# Gagabiro_POC_amp_main.net
KiCad netlist of a schematic drawn in Altium Designer
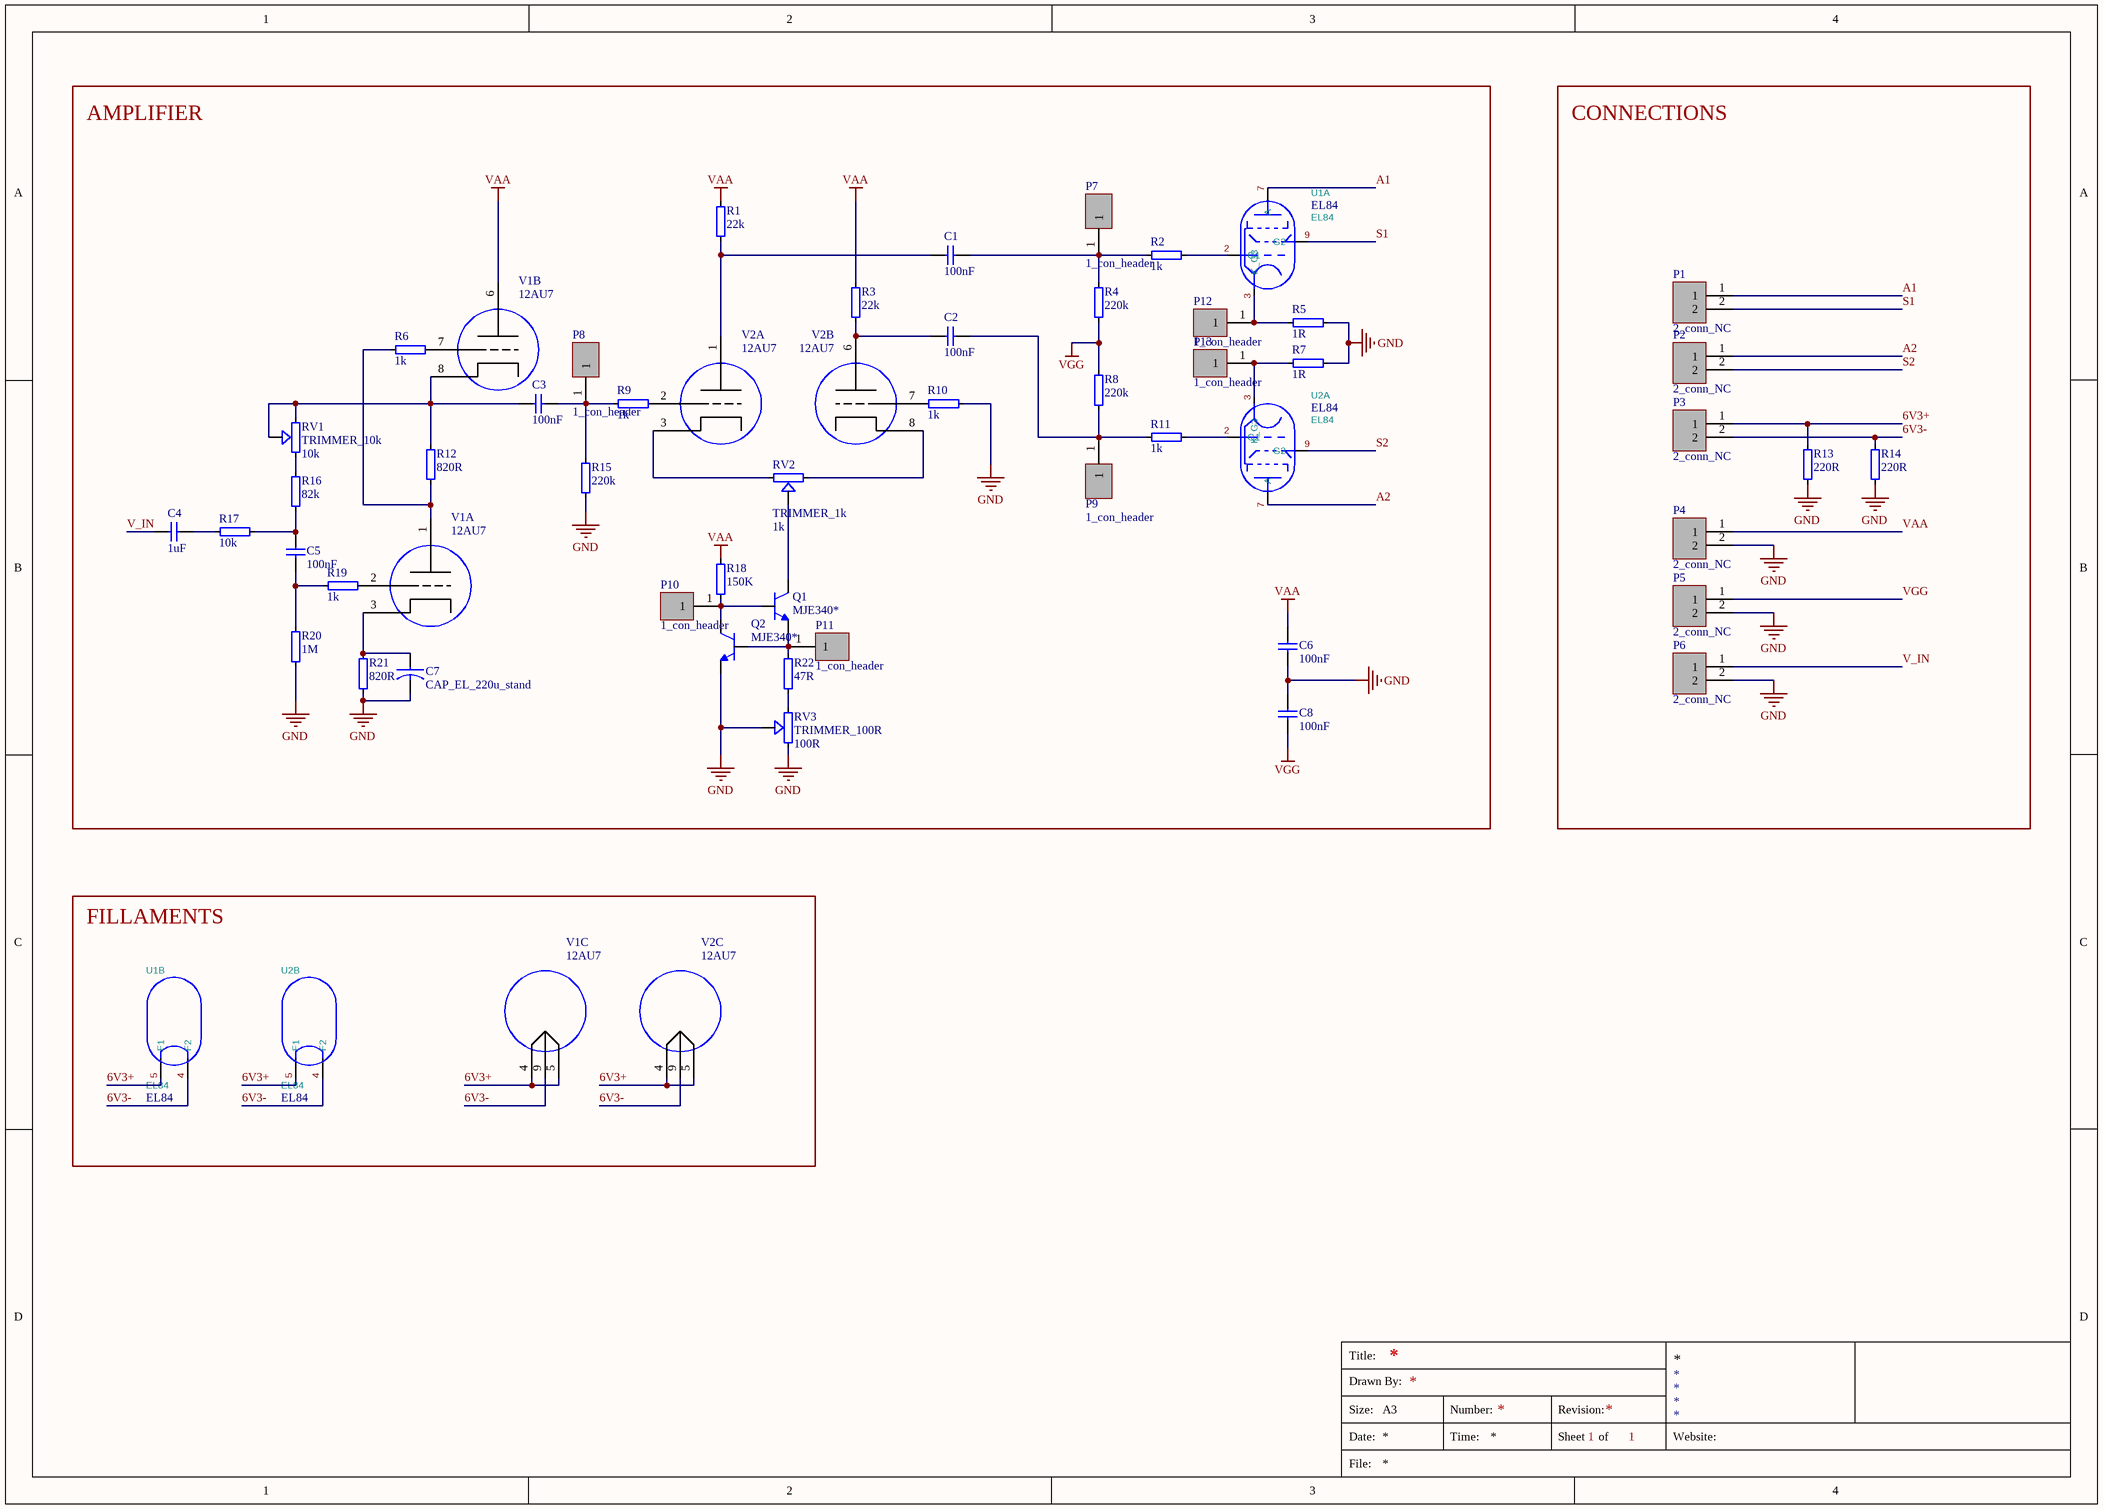
[diagram p0: Gagabiro_POC_amp_main.SchDoc]

(export (version "E")
  (design (tool "Eeschema 10.0.6"))
  (components
    (comp (ref "C1")
      (value "100nF")
      (footprint "CAP_panassonic_100n_450V")
      (description "Capacitor, Silver Mica")
      (fields (field (name "PART NUMBER") "CMICA_47PF"))
      (libsource (lib "Persephone_Integrated_Library") (part "CAP_POLY_100n"))
    )
    (comp (ref "C2")
      (value "100nF")
      (footprint "CAP_panassonic_100n_450V")
      (description "Capacitor, Silver Mica")
      (fields (field (name "PART NUMBER") "CMICA_47PF"))
      (libsource (lib "Persephone_Integrated_Library") (part "CAP_POLY_100n"))
    )
    (comp (ref "C3")
      (value "100nF")
      (footprint "CAP_panassonic_100n_450V")
      (description "Capacitor, Silver Mica")
      (fields (field (name "PART NUMBER") "CMICA_47PF"))
      (libsource (lib "Persephone_Integrated_Library") (part "CAP_POLY_100n"))
    )
    (comp (ref "C4")
      (value "1uF")
      (footprint "CAP_panassonic_1u_450V")
      (description "Capacitor, Silver Mica")
      (fields (field (name "PART NUMBER") "CMICA_47PF"))
      (libsource (lib "Persephone_Integrated_Library") (part "CAP_POLY_1u"))
    )
    (comp (ref "C5")
      (value "100nF")
      (footprint "CAP_panassonic_100n_450V")
      (description "Capacitor, Silver Mica")
      (fields (field (name "PART NUMBER") "CMICA_47PF"))
      (libsource (lib "Persephone_Integrated_Library") (part "CAP_POLY_100n"))
    )
    (comp (ref "C6")
      (value "100nF")
      (footprint "CAP_panassonic_100n_450V")
      (description "Capacitor, Silver Mica")
      (fields (field (name "PART NUMBER") "CMICA_47PF"))
      (libsource (lib "Persephone_Integrated_Library") (part "CAP_POLY_100n"))
    )
    (comp (ref "C7")
      (value "CAP_EL_220u_stand")
      (footprint "CAPPRD500W50D630H1120_stand")
      (description "220F 16V Aluminum Electrolytic Capacitors Radial, Can 1000 Hrs @ 105C")
      (fields (field (name "MP") "EEU-HD1C221B") (field (name "MF") "Panasonic"))
      (libsource (lib "Persephone_Integrated_Library") (part "CAP_EL_220u_stand"))
    )
    (comp (ref "C8")
      (value "100nF")
      (footprint "CAP_panassonic_100n_450V")
      (description "Capacitor, Silver Mica")
      (fields (field (name "PART NUMBER") "CMICA_47PF"))
      (libsource (lib "Persephone_Integrated_Library") (part "CAP_POLY_100n"))
    )
    (comp (ref "P1")
      (value "2_conn_NC")
      (footprint "2_conn_NC")
      (description "Connector Header Surface Mount, Right Angle 2 position 0.079 (2.00mm)")
      (fields (field (name "MP") "S2B-PH-SM4-TB") (field (name "MF") "JST Sales"))
      (libsource (lib "Gagabiro_Integrated_Library") (part "2_conn_NC"))
    )
    (comp (ref "P2")
      (value "2_conn_NC")
      (footprint "2_conn_NC")
      (description "Connector Header Surface Mount, Right Angle 2 position 0.079 (2.00mm)")
      (fields (field (name "MP") "S2B-PH-SM4-TB") (field (name "MF") "JST Sales"))
      (libsource (lib "Gagabiro_Integrated_Library") (part "2_conn_NC"))
    )
    (comp (ref "P3")
      (value "2_conn_NC")
      (footprint "2_conn_NC")
      (description "Connector Header Surface Mount, Right Angle 2 position 0.079 (2.00mm)")
      (fields (field (name "MP") "S2B-PH-SM4-TB") (field (name "MF") "JST Sales"))
      (libsource (lib "Gagabiro_Integrated_Library") (part "2_conn_NC"))
    )
    (comp (ref "P4")
      (value "2_conn_NC")
      (footprint "2_conn_NC")
      (description "Connector Header Surface Mount, Right Angle 2 position 0.079 (2.00mm)")
      (fields (field (name "MP") "S2B-PH-SM4-TB") (field (name "MF") "JST Sales"))
      (libsource (lib "Gagabiro_Integrated_Library") (part "2_conn_NC"))
    )
    (comp (ref "P5")
      (value "2_conn_NC")
      (footprint "2_conn_NC")
      (description "Connector Header Surface Mount, Right Angle 2 position 0.079 (2.00mm)")
      (fields (field (name "MP") "S2B-PH-SM4-TB") (field (name "MF") "JST Sales"))
      (libsource (lib "Gagabiro_Integrated_Library") (part "2_conn_NC"))
    )
    (comp (ref "P6")
      (value "2_conn_NC")
      (footprint "2_conn_NC")
      (description "Connector Header Surface Mount, Right Angle 2 position 0.079 (2.00mm)")
      (fields (field (name "MP") "S2B-PH-SM4-TB") (field (name "MF") "JST Sales"))
      (libsource (lib "Gagabiro_Integrated_Library") (part "2_conn_NC"))
    )
    (comp (ref "P7")
      (value "1_con_header")
      (footprint "SAMTEC_MTMM-101-X-X-S-X")
      (description "Connector Header Surface Mount, Right Angle 2 position 0.079 (2.00mm)")
      (fields (field (name "MP") "S2B-PH-SM4-TB") (field (name "MF") "JST Sales"))
      (libsource (lib "") (part "1_con_header_3"))
    )
    (comp (ref "P8")
      (value "1_con_header")
      (footprint "SAMTEC_MTMM-101-X-X-S-X")
      (description "Connector Header Surface Mount, Right Angle 2 position 0.079 (2.00mm)")
      (fields (field (name "MP") "S2B-PH-SM4-TB") (field (name "MF") "JST Sales"))
      (libsource (lib "") (part "1_con_header_3"))
    )
    (comp (ref "P9")
      (value "1_con_header")
      (footprint "SAMTEC_MTMM-101-X-X-S-X")
      (description "Connector Header Surface Mount, Right Angle 2 position 0.079 (2.00mm)")
      (fields (field (name "MP") "S2B-PH-SM4-TB") (field (name "MF") "JST Sales"))
      (libsource (lib "") (part "1_con_header_2"))
    )
    (comp (ref "P10")
      (value "1_con_header")
      (footprint "SAMTEC_MTMM-101-X-X-S-X")
      (description "Connector Header Surface Mount, Right Angle 2 position 0.079 (2.00mm)")
      (fields (field (name "MP") "S2B-PH-SM4-TB") (field (name "MF") "JST Sales"))
      (libsource (lib "Gagabiro") (part "1_con_header"))
    )
    (comp (ref "P11")
      (value "1_con_header")
      (footprint "SAMTEC_MTMM-101-X-X-S-X")
      (description "Connector Header Surface Mount, Right Angle 2 position 0.079 (2.00mm)")
      (fields (field (name "MP") "S2B-PH-SM4-TB") (field (name "MF") "JST Sales"))
      (libsource (lib "") (part "1_con_header_1"))
    )
    (comp (ref "P12")
      (value "1_con_header")
      (footprint "SAMTEC_MTMM-101-X-X-S-X")
      (description "Connector Header Surface Mount, Right Angle 2 position 0.079 (2.00mm)")
      (fields (field (name "MP") "S2B-PH-SM4-TB") (field (name "MF") "JST Sales"))
      (libsource (lib "Gagabiro") (part "1_con_header"))
    )
    (comp (ref "P13")
      (value "1_con_header")
      (footprint "SAMTEC_MTMM-101-X-X-S-X")
      (description "Connector Header Surface Mount, Right Angle 2 position 0.079 (2.00mm)")
      (fields (field (name "MP") "S2B-PH-SM4-TB") (field (name "MF") "JST Sales"))
      (libsource (lib "Gagabiro") (part "1_con_header"))
    )
    (comp (ref "Q1")
      (value "MJE340*")
      (footprint "TO126")
      (description "Bipolar (BJT) Transistor NPN 300 V 500 mA - 20.8 W Through Hole SOT-32-3")
      (fields (field (name "MF") "STMicroelectronics") (field (name "MP") "MJE340"))
      (libsource (lib "Persephone_Integrated_Library") (part "MJE340*"))
    )
    (comp (ref "Q2")
      (value "MJE340*")
      (footprint "TO126")
      (description "Bipolar (BJT) Transistor NPN 300 V 500 mA - 20.8 W Through Hole SOT-32-3")
      (fields (field (name "MF") "STMicroelectronics") (field (name "MP") "MJE340"))
      (libsource (lib "Persephone_Integrated_Library") (part "MJE340*"))
    )
    (comp (ref "R1")
      (value "22k")
      (footprint "RES_2W_vertical")
      (description "Resistor, 2W")
      (fields (field (name "PART NUMBER") "R2W") (field (name "AUTHOR") "colombari"))
      (libsource (lib "Gagabiro_Integrated_Library") (part "R_2W_vertical_22k"))
    )
    (comp (ref "R2")
      (value "1k")
      (footprint "RES_2W_vertical")
      (description "Resistor, 2W")
      (fields (field (name "PART NUMBER") "R2W") (field (name "AUTHOR") "colombari"))
      (libsource (lib "Gagabiro_Integrated_Library") (part "R_2W_vertical_1k"))
    )
    (comp (ref "R3")
      (value "22k")
      (footprint "RES_2W_vertical")
      (description "Resistor, 2W")
      (fields (field (name "PART NUMBER") "R2W") (field (name "AUTHOR") "colombari"))
      (libsource (lib "Gagabiro_Integrated_Library") (part "R_2W_vertical_22k"))
    )
    (comp (ref "R4")
      (value "220k")
      (footprint "RES_2W_vertical")
      (description "Resistor, 2W")
      (fields (field (name "PART NUMBER") "R2W") (field (name "AUTHOR") "colombari"))
      (libsource (lib "Gagabiro_Integrated_Library") (part "R_2W_vertical_220k"))
    )
    (comp (ref "R5")
      (value "1R")
      (footprint "RES_2W_vertical")
      (description "Resistor, 2W")
      (fields (field (name "PART NUMBER") "R2W") (field (name "AUTHOR") "colombari"))
      (libsource (lib "Gagabiro_Integrated_Library") (part "R_2W_vertical_1R"))
    )
    (comp (ref "R6")
      (value "1k")
      (footprint "RES_2W_vertical")
      (description "Resistor, 2W")
      (fields (field (name "PART NUMBER") "R2W") (field (name "AUTHOR") "colombari"))
      (libsource (lib "Gagabiro_Integrated_Library") (part "R_2W_vertical_1k"))
    )
    (comp (ref "R7")
      (value "1R")
      (footprint "RES_2W_vertical")
      (description "Resistor, 2W")
      (fields (field (name "PART NUMBER") "R2W") (field (name "AUTHOR") "colombari"))
      (libsource (lib "Gagabiro_Integrated_Library") (part "R_2W_vertical_1R"))
    )
    (comp (ref "R8")
      (value "220k")
      (footprint "RES_2W_vertical")
      (description "Resistor, 2W")
      (fields (field (name "PART NUMBER") "R2W") (field (name "AUTHOR") "colombari"))
      (libsource (lib "Gagabiro_Integrated_Library") (part "R_2W_vertical_220k"))
    )
    (comp (ref "R9")
      (value "1k")
      (footprint "RES_2W_vertical")
      (description "Resistor, 2W")
      (fields (field (name "PART NUMBER") "R2W") (field (name "AUTHOR") "colombari"))
      (libsource (lib "Gagabiro_Integrated_Library") (part "R_2W_vertical_1k"))
    )
    (comp (ref "R10")
      (value "1k")
      (footprint "RES_2W_vertical")
      (description "Resistor, 2W")
      (fields (field (name "PART NUMBER") "R2W") (field (name "AUTHOR") "colombari"))
      (libsource (lib "Gagabiro_Integrated_Library") (part "R_2W_vertical_1k"))
    )
    (comp (ref "R11")
      (value "1k")
      (footprint "RES_2W_vertical")
      (description "Resistor, 2W")
      (fields (field (name "PART NUMBER") "R2W") (field (name "AUTHOR") "colombari"))
      (libsource (lib "Gagabiro_Integrated_Library") (part "R_2W_vertical_1k"))
    )
    (comp (ref "R12")
      (value "820R")
      (footprint "RES_2W_vertical")
      (description "Resistor, 2W")
      (fields (field (name "PART NUMBER") "R2W") (field (name "AUTHOR") "colombari"))
      (libsource (lib "Gagabiro_Integrated_Library") (part "R_2W_vertical_820R"))
    )
    (comp (ref "R13")
      (value "220R")
      (footprint "RES_2W_vertical")
      (description "Resistor, 2W")
      (fields (field (name "PART NUMBER") "R2W") (field (name "AUTHOR") "colombari"))
      (libsource (lib "Persephone_Integrated_Library") (part "R_2W_vertical_220R"))
    )
    (comp (ref "R14")
      (value "220R")
      (footprint "RES_2W_vertical")
      (description "Resistor, 2W")
      (fields (field (name "PART NUMBER") "R2W") (field (name "AUTHOR") "colombari"))
      (libsource (lib "Persephone_Integrated_Library") (part "R_2W_vertical_220R"))
    )
    (comp (ref "R15")
      (value "220k")
      (footprint "RES_2W_vertical")
      (description "Resistor, 2W")
      (fields (field (name "PART NUMBER") "R2W") (field (name "AUTHOR") "colombari"))
      (libsource (lib "Gagabiro_Integrated_Library") (part "R_2W_vertical_220k"))
    )
    (comp (ref "R16")
      (value "82k")
      (footprint "RES_2W_vertical")
      (description "Resistor, 2W")
      (fields (field (name "PART NUMBER") "R2W") (field (name "AUTHOR") "colombari"))
      (libsource (lib "Gagabiro_Integrated_Library") (part "R_2W_vertical_82k"))
    )
    (comp (ref "R17")
      (value "10k")
      (footprint "RES_2W_vertical")
      (description "Resistor, 2W")
      (fields (field (name "PART NUMBER") "R2W") (field (name "AUTHOR") "colombari"))
      (libsource (lib "Gagabiro_Integrated_Library") (part "R_2W_vertical_10k"))
    )
    (comp (ref "R18")
      (value "150K")
      (footprint "RES_2W_vertical")
      (description "Resistor, 2W")
      (fields (field (name "PART NUMBER") "R2W") (field (name "AUTHOR") "colombari"))
      (libsource (lib "Gagabiro_Integrated_Library") (part "R_2W_vertical_150K"))
    )
    (comp (ref "R19")
      (value "1k")
      (footprint "RES_2W_vertical")
      (description "Resistor, 2W")
      (fields (field (name "PART NUMBER") "R2W") (field (name "AUTHOR") "colombari"))
      (libsource (lib "Gagabiro_Integrated_Library") (part "R_2W_vertical_1k"))
    )
    (comp (ref "R20")
      (value "1M")
      (footprint "RES_2W_vertical")
      (description "Resistor, 2W")
      (fields (field (name "PART NUMBER") "R2W") (field (name "AUTHOR") "colombari"))
      (libsource (lib "Gagabiro_Integrated_Library") (part "R_2W_vertical_1M"))
    )
    (comp (ref "R21")
      (value "820R")
      (footprint "RES_2W_vertical")
      (description "Resistor, 2W")
      (fields (field (name "PART NUMBER") "R2W") (field (name "AUTHOR") "colombari"))
      (libsource (lib "Gagabiro_Integrated_Library") (part "R_2W_vertical_820R"))
    )
    (comp (ref "R22")
      (value "47R")
      (footprint "RES_2W_vertical")
      (description "Resistor, 2W")
      (fields (field (name "PART NUMBER") "R2W") (field (name "AUTHOR") "colombari"))
      (libsource (lib "Gagabiro_Integrated_Library") (part "R_2W_vertical_47R"))
    )
    (comp (ref "RV1")
      (value "TRIMMER_10k")
      (footprint "TRIM_PV36W204C01B00 - duplicate")
      (description "TRIMMER")
      (fields
        (field (name "MF") "Bourns Electronics")
        (field (name "MP") "PV36W204C01B00.")
        (field (name "ALTIUM_VALUE") "10k")
      )
      (libsource (lib "Persephone_Integrated_Library") (part "TRIMMER_10k"))
    )
    (comp (ref "RV2")
      (value "TRIMMER_1k")
      (footprint "TRIM_PV36W204C01B00 - duplicate")
      (description "TRIMMER")
      (fields
        (field (name "MF") "Bourns Electronics")
        (field (name "MP") "PV36W204C01B00.")
        (field (name "ALTIUM_VALUE") "1k")
      )
      (libsource (lib "Persephone_Integrated_Library") (part "TRIMMER_1k"))
    )
    (comp (ref "RV3")
      (value "TRIMMER_100R")
      (footprint "TRIM_PV36W204C01B00 - duplicate")
      (description "TRIMMER")
      (fields
        (field (name "MF") "Bourns Electronics")
        (field (name "MP") "PV36W204C01B00.")
        (field (name "ALTIUM_VALUE") "100R")
      )
      (libsource (lib "Persephone") (part "TRIMMER_100R"))
    )
    (comp (ref "U1")
      (value "EL84")
      (footprint "EL84")
      (fields (field (name "ALTIUM_VALUE") "EL84"))
      (libsource (lib "Gagabiro_Integrated_Library") (part "EL84"))
    )
    (comp (ref "U2")
      (value "EL84")
      (footprint "EL84")
      (fields (field (name "ALTIUM_VALUE") "EL84"))
      (libsource (lib "Gagabiro_Integrated_Library") (part "EL84"))
    )
    (comp (ref "V1")
      (value "12AU7")
      (footprint "12A_7")
      (description "TUNGSOL 12AU7 NEW PRD PREAMP TB")
      (fields (field (name "MF") "RCA") (field (name "MP") "12AX7"))
      (libsource (lib "") (part "12AU7_1"))
    )
    (comp (ref "V2")
      (value "12AU7")
      (footprint "12A_7")
      (description "TUNGSOL 12AU7 NEW PRD PREAMP TB")
      (fields (field (name "MF") "RCA") (field (name "MP") "12AX7"))
      (libsource (lib "Gagabiro_Integrated_Library") (part "12AU7"))
    )
  )
  (nets
    (net (code "1") (name "/6V3+") (class "Default")
      (node (ref "P3") (pin "1") (pinfunction "1_1") (pintype "passive"))
      (node (ref "R13") (pin "2") (pinfunction "2_2") (pintype "passive"))
      (node (ref "U1") (pin "5") (pinfunction "F1_5") (pintype "passive"))
      (node (ref "U2") (pin "5") (pinfunction "F1_5") (pintype "passive"))
      (node (ref "V1") (pin "4") (pinfunction "4_4") (pintype "passive"))
      (node (ref "V1") (pin "5") (pinfunction "5_5") (pintype "passive"))
      (node (ref "V2") (pin "4") (pinfunction "4_4") (pintype "passive"))
      (node (ref "V2") (pin "5") (pinfunction "5_5") (pintype "passive"))
    )
    (net (code "2") (name "/6V3-") (class "Default")
      (node (ref "P3") (pin "2") (pinfunction "2_2") (pintype "passive"))
      (node (ref "R14") (pin "2") (pinfunction "2_2") (pintype "passive"))
      (node (ref "U1") (pin "4") (pinfunction "F2_4") (pintype "passive"))
      (node (ref "U2") (pin "4") (pinfunction "F2_4") (pintype "passive"))
      (node (ref "V1") (pin "9") (pinfunction "9_9") (pintype "passive"))
      (node (ref "V2") (pin "9") (pinfunction "9_9") (pintype "passive"))
    )
    (net (code "3") (name "/A1") (class "Default")
      (node (ref "P1") (pin "1") (pinfunction "1_1") (pintype "passive"))
      (node (ref "U1") (pin "7") (pinfunction "A_7") (pintype "passive"))
    )
    (net (code "4") (name "/A2") (class "Default")
      (node (ref "P2") (pin "1") (pinfunction "1_1") (pintype "passive"))
      (node (ref "U2") (pin "7") (pinfunction "A_7") (pintype "passive"))
    )
    (net (code "5") (name "/S1") (class "Default")
      (node (ref "P1") (pin "2") (pinfunction "2_2") (pintype "passive"))
      (node (ref "U1") (pin "9") (pinfunction "G2_9") (pintype "passive"))
    )
    (net (code "6") (name "/S2") (class "Default")
      (node (ref "P2") (pin "2") (pinfunction "2_2") (pintype "passive"))
      (node (ref "U2") (pin "9") (pinfunction "G2_9") (pintype "passive"))
    )
    (net (code "7") (name "/V_IN") (class "Default")
      (node (ref "C4") (pin "1") (pinfunction "1_1") (pintype "passive"))
      (node (ref "P6") (pin "1") (pinfunction "1_1") (pintype "passive"))
    )
    (net (code "8") (name "GND") (class "Default")
      (node (ref "C6") (pin "1") (pinfunction "1_1") (pintype "passive"))
      (node (ref "C7") (pin "N") (pinfunction "N_N") (pintype "passive"))
      (node (ref "C8") (pin "1") (pinfunction "1_1") (pintype "passive"))
      (node (ref "P4") (pin "2") (pinfunction "2_2") (pintype "passive"))
      (node (ref "P5") (pin "2") (pinfunction "2_2") (pintype "passive"))
      (node (ref "P6") (pin "2") (pinfunction "2_2") (pintype "passive"))
      (node (ref "Q2") (pin "1") (pinfunction "E_1") (pintype "passive"))
      (node (ref "R10") (pin "2") (pinfunction "2_2") (pintype "passive"))
      (node (ref "R13") (pin "1") (pinfunction "1_1") (pintype "passive"))
      (node (ref "R14") (pin "1") (pinfunction "1_1") (pintype "passive"))
      (node (ref "R15") (pin "1") (pinfunction "1_1") (pintype "passive"))
      (node (ref "R20") (pin "1") (pinfunction "1_1") (pintype "passive"))
      (node (ref "R21") (pin "1") (pinfunction "1_1") (pintype "passive"))
      (node (ref "R5") (pin "2") (pinfunction "2_2") (pintype "passive"))
      (node (ref "R7") (pin "2") (pinfunction "2_2") (pintype "passive"))
      (node (ref "RV3") (pin "1") (pinfunction "1_1") (pintype "passive"))
      (node (ref "RV3") (pin "2") (pinfunction "2_2") (pintype "passive"))
    )
    (net (code "9") (name "Net-(C1-Pad1)") (class "Default")
      (node (ref "C1") (pin "1") (pinfunction "1_1") (pintype "passive"))
      (node (ref "R1") (pin "1") (pinfunction "1_1") (pintype "passive"))
      (node (ref "V2") (pin "1") (pinfunction "1_1") (pintype "passive"))
    )
    (net (code "10") (name "Net-(C1-Pad2)") (class "Default")
      (node (ref "C1") (pin "2") (pinfunction "2_2") (pintype "passive"))
      (node (ref "P7") (pin "1") (pinfunction "1_1") (pintype "passive"))
      (node (ref "R2") (pin "1") (pinfunction "1_1") (pintype "passive"))
      (node (ref "R4") (pin "2") (pinfunction "2_2") (pintype "passive"))
    )
    (net (code "11") (name "Net-(C2-Pad1)") (class "Default")
      (node (ref "C2") (pin "1") (pinfunction "1_1") (pintype "passive"))
      (node (ref "R3") (pin "1") (pinfunction "1_1") (pintype "passive"))
      (node (ref "V2") (pin "6") (pinfunction "6_6") (pintype "passive"))
    )
    (net (code "12") (name "Net-(C2-Pad2)") (class "Default")
      (node (ref "C2") (pin "2") (pinfunction "2_2") (pintype "passive"))
      (node (ref "P9") (pin "1") (pinfunction "1_1") (pintype "passive"))
      (node (ref "R11") (pin "1") (pinfunction "1_1") (pintype "passive"))
      (node (ref "R8") (pin "2") (pinfunction "2_2") (pintype "passive"))
    )
    (net (code "13") (name "Net-(C3-Pad1)") (class "Default")
      (node (ref "C3") (pin "1") (pinfunction "1_1") (pintype "passive"))
      (node (ref "R12") (pin "2") (pinfunction "2_2") (pintype "passive"))
      (node (ref "RV1") (pin "2") (pinfunction "2_2") (pintype "passive"))
      (node (ref "RV1") (pin "3") (pinfunction "3_3") (pintype "passive"))
      (node (ref "V1") (pin "8") (pinfunction "8_8") (pintype "passive"))
    )
    (net (code "14") (name "Net-(C3-Pad2)") (class "Default")
      (node (ref "C3") (pin "2") (pinfunction "2_2") (pintype "passive"))
      (node (ref "P8") (pin "1") (pinfunction "1_1") (pintype "passive"))
      (node (ref "R15") (pin "2") (pinfunction "2_2") (pintype "passive"))
      (node (ref "R9") (pin "1") (pinfunction "1_1") (pintype "passive"))
    )
    (net (code "15") (name "Net-(C4-Pad2)") (class "Default")
      (node (ref "C4") (pin "2") (pinfunction "2_2") (pintype "passive"))
      (node (ref "R17") (pin "1") (pinfunction "1_1") (pintype "passive"))
    )
    (net (code "16") (name "Net-(C5-Pad1)") (class "Default")
      (node (ref "C5") (pin "1") (pinfunction "1_1") (pintype "passive"))
      (node (ref "R19") (pin "1") (pinfunction "1_1") (pintype "passive"))
      (node (ref "R20") (pin "2") (pinfunction "2_2") (pintype "passive"))
    )
    (net (code "17") (name "Net-(C5-Pad2)") (class "Default")
      (node (ref "C5") (pin "2") (pinfunction "2_2") (pintype "passive"))
      (node (ref "R16") (pin "1") (pinfunction "1_1") (pintype "passive"))
      (node (ref "R17") (pin "2") (pinfunction "2_2") (pintype "passive"))
    )
    (net (code "18") (name "Net-(C7-PadP)") (class "Default")
      (node (ref "C7") (pin "P") (pinfunction "P_P") (pintype "passive"))
      (node (ref "R21") (pin "2") (pinfunction "2_2") (pintype "passive"))
      (node (ref "V1") (pin "3") (pinfunction "3_3") (pintype "passive"))
    )
    (net (code "19") (name "Net-(Q1-B)") (class "Default")
      (node (ref "P10") (pin "1") (pinfunction "1_1") (pintype "passive"))
      (node (ref "Q1") (pin "3") (pinfunction "B_3") (pintype "passive"))
      (node (ref "Q2") (pin "2") (pinfunction "C_2") (pintype "passive"))
      (node (ref "R18") (pin "1") (pinfunction "1_1") (pintype "passive"))
    )
    (net (code "20") (name "Net-(Q1-C)") (class "Default")
      (node (ref "Q1") (pin "2") (pinfunction "C_2") (pintype "passive"))
      (node (ref "RV2") (pin "2") (pinfunction "2_2") (pintype "passive"))
    )
    (net (code "21") (name "Net-(Q1-E)") (class "Default")
      (node (ref "P11") (pin "1") (pinfunction "1_1") (pintype "passive"))
      (node (ref "Q1") (pin "1") (pinfunction "E_1") (pintype "passive"))
      (node (ref "Q2") (pin "3") (pinfunction "B_3") (pintype "passive"))
      (node (ref "R22") (pin "2") (pinfunction "2_2") (pintype "passive"))
    )
    (net (code "22") (name "Net-(R6-Pad2)") (class "Default")
      (node (ref "R6") (pin "2") (pinfunction "2_2") (pintype "passive"))
      (node (ref "V1") (pin "7") (pinfunction "7_7") (pintype "passive"))
    )
    (net (code "23") (name "Net-(R9-Pad2)") (class "Default")
      (node (ref "R9") (pin "2") (pinfunction "2_2") (pintype "passive"))
      (node (ref "V2") (pin "2") (pinfunction "2_2") (pintype "passive"))
    )
    (net (code "24") (name "Net-(R10-Pad1)") (class "Default")
      (node (ref "R10") (pin "1") (pinfunction "1_1") (pintype "passive"))
      (node (ref "V2") (pin "7") (pinfunction "7_7") (pintype "passive"))
    )
    (net (code "25") (name "Net-(R12-Pad1)") (class "Default")
      (node (ref "R12") (pin "1") (pinfunction "1_1") (pintype "passive"))
      (node (ref "R6") (pin "1") (pinfunction "1_1") (pintype "passive"))
      (node (ref "V1") (pin "1") (pinfunction "1_1") (pintype "passive"))
    )
    (net (code "26") (name "Net-(R16-Pad2)") (class "Default")
      (node (ref "R16") (pin "2") (pinfunction "2_2") (pintype "passive"))
      (node (ref "RV1") (pin "1") (pinfunction "1_1") (pintype "passive"))
    )
    (net (code "27") (name "Net-(R19-Pad2)") (class "Default")
      (node (ref "R19") (pin "2") (pinfunction "2_2") (pintype "passive"))
      (node (ref "V1") (pin "2") (pinfunction "2_2") (pintype "passive"))
    )
    (net (code "28") (name "Net-(R22-Pad1)") (class "Default")
      (node (ref "R22") (pin "1") (pinfunction "1_1") (pintype "passive"))
      (node (ref "RV3") (pin "3") (pinfunction "3_3") (pintype "passive"))
    )
    (net (code "29") (name "Net-(RV2-Pad1)") (class "Default")
      (node (ref "RV2") (pin "1") (pinfunction "1_1") (pintype "passive"))
      (node (ref "V2") (pin "8") (pinfunction "8_8") (pintype "passive"))
    )
    (net (code "30") (name "Net-(RV2-Pad3)") (class "Default")
      (node (ref "RV2") (pin "3") (pinfunction "3_3") (pintype "passive"))
      (node (ref "V2") (pin "3") (pinfunction "3_3") (pintype "passive"))
    )
    (net (code "31") (name "Net-(U1A-G1)") (class "Default")
      (node (ref "R2") (pin "2") (pinfunction "2_2") (pintype "passive"))
      (node (ref "U1") (pin "2") (pinfunction "G1_2") (pintype "passive"))
    )
    (net (code "32") (name "Net-(U1A-K_G3)") (class "Default")
      (node (ref "P12") (pin "1") (pinfunction "1_1") (pintype "passive"))
      (node (ref "R5") (pin "1") (pinfunction "1_1") (pintype "passive"))
      (node (ref "U1") (pin "3") (pinfunction "K_G3_3") (pintype "passive"))
    )
    (net (code "33") (name "Net-(U2A-G1)") (class "Default")
      (node (ref "R11") (pin "2") (pinfunction "2_2") (pintype "passive"))
      (node (ref "U2") (pin "2") (pinfunction "G1_2") (pintype "passive"))
    )
    (net (code "34") (name "Net-(U2A-K_G3)") (class "Default")
      (node (ref "P13") (pin "1") (pinfunction "1_1") (pintype "passive"))
      (node (ref "R7") (pin "1") (pinfunction "1_1") (pintype "passive"))
      (node (ref "U2") (pin "3") (pinfunction "K_G3_3") (pintype "passive"))
    )
    (net (code "35") (name "VAA") (class "Default")
      (node (ref "C6") (pin "2") (pinfunction "2_2") (pintype "passive"))
      (node (ref "P4") (pin "1") (pinfunction "1_1") (pintype "passive"))
      (node (ref "R1") (pin "2") (pinfunction "2_2") (pintype "passive"))
      (node (ref "R18") (pin "2") (pinfunction "2_2") (pintype "passive"))
      (node (ref "R3") (pin "2") (pinfunction "2_2") (pintype "passive"))
      (node (ref "V1") (pin "6") (pinfunction "6_6") (pintype "passive"))
    )
    (net (code "36") (name "VGG") (class "Default")
      (node (ref "C8") (pin "2") (pinfunction "2_2") (pintype "passive"))
      (node (ref "P5") (pin "1") (pinfunction "1_1") (pintype "passive"))
      (node (ref "R4") (pin "1") (pinfunction "1_1") (pintype "passive"))
      (node (ref "R8") (pin "1") (pinfunction "1_1") (pintype "passive"))
    )
  )
)
